# current_amplification.net
KiCad netlist of a schematic drawn in Altium Designer
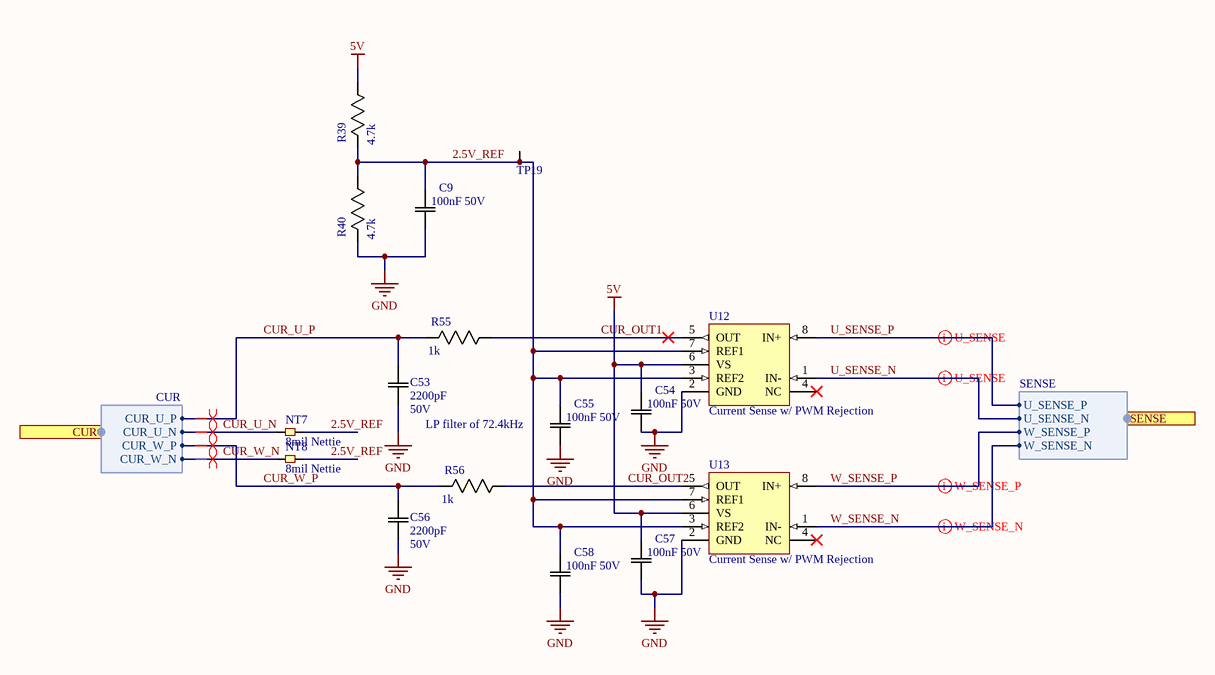
[diagram p0: current_amplification.SchDoc]

(export (version "E")
  (design (tool "Eeschema 10.0.6"))
  (components
    (comp (ref "C9")
      (value "100nF 50V")
      (footprint "0603")
      (description "Default Symbol for Capacitors")
      (fields (field (name "TOLERANCE") "10%") (field (name "PART NUMBER") "CAP 100nF 50V"))
      (libsource (lib "capacitor_library") (part "CAP_Default"))
    )
    (comp (ref "C53")
      (value "2200pF")
      (footprint "0603")
      (description "Default Symbol for Capacitors")
      (fields
        (field (name "TOLERANCE") "10%")
        (field (name "RATING") "50V")
        (field (name "PART NUMBER") "CAP 2200pF 50V")
      )
      (libsource (lib "capacitor_library") (part "CAP_Default"))
    )
    (comp (ref "C54")
      (value "100nF 50V")
      (footprint "0603")
      (description "Default Symbol for Capacitors")
      (fields (field (name "TOLERANCE") "10%") (field (name "PART NUMBER") "CAP 100nF 50V"))
      (libsource (lib "capacitor_library") (part "CAP_Default"))
    )
    (comp (ref "C55")
      (value "100nF 50V")
      (footprint "0603")
      (description "Default Symbol for Capacitors")
      (fields (field (name "TOLERANCE") "10%") (field (name "PART NUMBER") "CAP 100nF 50V"))
      (libsource (lib "capacitor_library") (part "CAP_Default"))
    )
    (comp (ref "C56")
      (value "2200pF")
      (footprint "0603")
      (description "Default Symbol for Capacitors")
      (fields
        (field (name "TOLERANCE") "10%")
        (field (name "RATING") "50V")
        (field (name "PART NUMBER") "CAP 2200pF 50V")
      )
      (libsource (lib "capacitor_library") (part "CAP_Default"))
    )
    (comp (ref "C57")
      (value "100nF 50V")
      (footprint "0603")
      (description "Default Symbol for Capacitors")
      (fields (field (name "TOLERANCE") "10%") (field (name "PART NUMBER") "CAP 100nF 50V"))
      (libsource (lib "capacitor_library") (part "CAP_Default"))
    )
    (comp (ref "C58")
      (value "100nF 50V")
      (footprint "0603")
      (description "Default Symbol for Capacitors")
      (fields (field (name "TOLERANCE") "10%") (field (name "PART NUMBER") "CAP 100nF 50V"))
      (libsource (lib "capacitor_library") (part "CAP_Default"))
    )
    (comp (ref "NT7")
      (value "8mil Nettie")
      (footprint "NT_8mil")
      (description "8mil wide nettie")
      (fields (field (name "PART NUMBER") "NT_8"))
      (libsource (lib "Resistor_Library") (part "NT_8"))
    )
    (comp (ref "NT8")
      (value "8mil Nettie")
      (footprint "NT_8mil")
      (description "8mil wide nettie")
      (fields (field (name "PART NUMBER") "NT_8"))
      (libsource (lib "Resistor_Library") (part "NT_8"))
    )
    (comp (ref "R39")
      (value "4.7k")
      (footprint "0603")
      (description "Default Resistor Symbol")
      (fields (field (name "TOLERANCE") "1%") (field (name "PART NUMBER") "RES 4.7k 1/8W - 1%"))
      (libsource (lib "Resistor_Library") (part "RES_DEFAULT"))
    )
    (comp (ref "R40")
      (value "4.7k")
      (footprint "0603")
      (description "Default Resistor Symbol")
      (fields (field (name "TOLERANCE") "1%") (field (name "PART NUMBER") "RES 4.7k 1/8W - 1%"))
      (libsource (lib "") (part "RES_DEFAULT_1"))
    )
    (comp (ref "R55")
      (value "1k")
      (footprint "0603")
      (description "Default Resistor Symbol")
      (fields (field (name "TOLERANCE") "1%") (field (name "PART NUMBER") "RES 1k 1/8W - 1%"))
      (libsource (lib "Resistor_Library") (part "RES_DEFAULT"))
    )
    (comp (ref "R56")
      (value "1k")
      (footprint "0603")
      (description "Default Resistor Symbol")
      (fields (field (name "TOLERANCE") "1%") (field (name "PART NUMBER") "RES 1k 1/8W - 1%"))
      (libsource (lib "Resistor_Library") (part "RES_DEFAULT"))
    )
    (comp (ref "TP19")
      (value "2.5V")
      (footprint "TP")
      (fields (field (name "PART NUMBER") "Test Point (Via)"))
      (libsource (lib "IC_Library") (part "Test Point (Via)"))
    )
    (comp (ref "U12")
      (value "Current Sense w/ PWM Rejection")
      (footprint "8-SOIC")
      (description "SP Amp Current Sense Amp Single R-R O/P 5.5V Automotive 6-Pin SC-70 T/R")
      (fields (field (name "PART NUMBER") "INA240A3EDRQ1"))
      (libsource (lib "IC_Library") (part "INA240A3EDRQ1"))
    )
    (comp (ref "U13")
      (value "Current Sense w/ PWM Rejection")
      (footprint "8-SOIC")
      (description "SP Amp Current Sense Amp Single R-R O/P 5.5V Automotive 6-Pin SC-70 T/R")
      (fields (field (name "PART NUMBER") "INA240A3EDRQ1"))
      (libsource (lib "IC_Library") (part "INA240A3EDRQ1"))
    )
  )
  (nets
    (net (code "3") (name "/2.5V_REF") (class "Default")
      (node (ref "C55") (pin "2") (pinfunction "C2_2") (pintype "passive"))
      (node (ref "C58") (pin "2") (pinfunction "C2_2") (pintype "passive"))
      (node (ref "C9") (pin "2") (pinfunction "C2_2") (pintype "passive"))
      (node (ref "NT7") (pin "2") (pinfunction "2_2") (pintype "passive"))
      (node (ref "NT8") (pin "2") (pinfunction "2_2") (pintype "passive"))
      (node (ref "R39") (pin "2") (pinfunction "R2_2") (pintype "passive"))
      (node (ref "R40") (pin "1") (pinfunction "R1_1") (pintype "passive"))
      (node (ref "TP19") (pin "1") (pinfunction "1_1") (pintype "passive"))
      (node (ref "U12") (pin "3") (pinfunction "REF2_3") (pintype "input"))
      (node (ref "U12") (pin "7") (pinfunction "REF1_7") (pintype "input"))
      (node (ref "U13") (pin "3") (pinfunction "REF2_3") (pintype "input"))
      (node (ref "U13") (pin "7") (pinfunction "REF1_7") (pintype "input"))
    )
    (net (code "4") (name "/CUR_OUT1") (class "Default")
      (node (ref "R55") (pin "1") (pinfunction "R1_1") (pintype "passive"))
      (node (ref "U12") (pin "5") (pinfunction "OUT_5") (pintype "output"))
    )
    (net (code "5") (name "/CUR_OUT2") (class "Default")
      (node (ref "R56") (pin "1") (pinfunction "R1_1") (pintype "passive"))
      (node (ref "U13") (pin "5") (pinfunction "OUT_5") (pintype "output"))
    )
    (net (code "6") (name "/CUR_U_N") (class "Default")
      (node (ref "NT7") (pin "1") (pinfunction "1_1") (pintype "passive"))
    )
    (net (code "7") (name "/CUR_U_P") (class "Default")
      (node (ref "C53") (pin "2") (pinfunction "C2_2") (pintype "passive"))
      (node (ref "R55") (pin "2") (pinfunction "R2_2") (pintype "passive"))
    )
    (net (code "8") (name "/CUR_W_N") (class "Default")
      (node (ref "NT8") (pin "1") (pinfunction "1_1") (pintype "passive"))
    )
    (net (code "9") (name "/CUR_W_P") (class "Default")
      (node (ref "C56") (pin "2") (pinfunction "C2_2") (pintype "passive"))
      (node (ref "R56") (pin "2") (pinfunction "R2_2") (pintype "passive"))
    )
    (net (code "10") (name "/U_SENSE_N") (class "Default")
      (node (ref "U12") (pin "1") (pinfunction "IN-_1") (pintype "input"))
    )
    (net (code "11") (name "/U_SENSE_P") (class "Default")
      (node (ref "U12") (pin "8") (pinfunction "IN+_8") (pintype "input"))
    )
    (net (code "12") (name "/W_SENSE_N") (class "Default")
      (node (ref "U13") (pin "1") (pinfunction "IN-_1") (pintype "input"))
    )
    (net (code "13") (name "/W_SENSE_P") (class "Default")
      (node (ref "U13") (pin "8") (pinfunction "IN+_8") (pintype "input"))
    )
    (net (code "16") (name "5V") (class "Default")
      (node (ref "C54") (pin "2") (pinfunction "C2_2") (pintype "passive"))
      (node (ref "C57") (pin "2") (pinfunction "C2_2") (pintype "passive"))
      (node (ref "R39") (pin "1") (pinfunction "R1_1") (pintype "passive"))
      (node (ref "U12") (pin "6") (pinfunction "VS_6") (pintype "power_in"))
      (node (ref "U13") (pin "6") (pinfunction "VS_6") (pintype "power_in"))
    )
    (net (code "17") (name "GND") (class "Default")
      (node (ref "C53") (pin "1") (pinfunction "C1_1") (pintype "passive"))
      (node (ref "C54") (pin "1") (pinfunction "C1_1") (pintype "passive"))
      (node (ref "C55") (pin "1") (pinfunction "C1_1") (pintype "passive"))
      (node (ref "C56") (pin "1") (pinfunction "C1_1") (pintype "passive"))
      (node (ref "C57") (pin "1") (pinfunction "C1_1") (pintype "passive"))
      (node (ref "C58") (pin "1") (pinfunction "C1_1") (pintype "passive"))
      (node (ref "C9") (pin "1") (pinfunction "C1_1") (pintype "passive"))
      (node (ref "R40") (pin "2") (pinfunction "R2_2") (pintype "passive"))
      (node (ref "U12") (pin "2") (pinfunction "GND_2") (pintype "power_in"))
      (node (ref "U13") (pin "2") (pinfunction "GND_2") (pintype "power_in"))
    )
    (net (code "18") (name "unconnected-(U12-NC-Pad4)") (class "Default")
      (node (ref "U12") (pin "4") (pinfunction "NC_4") (pintype "passive+no_connect"))
    )
    (net (code "19") (name "unconnected-(U13-NC-Pad4)") (class "Default")
      (node (ref "U13") (pin "4") (pinfunction "NC_4") (pintype "passive+no_connect"))
    )
  )
)
